# FrontPanel.net
KiCad netlist of a schematic drawn in Altium Designer
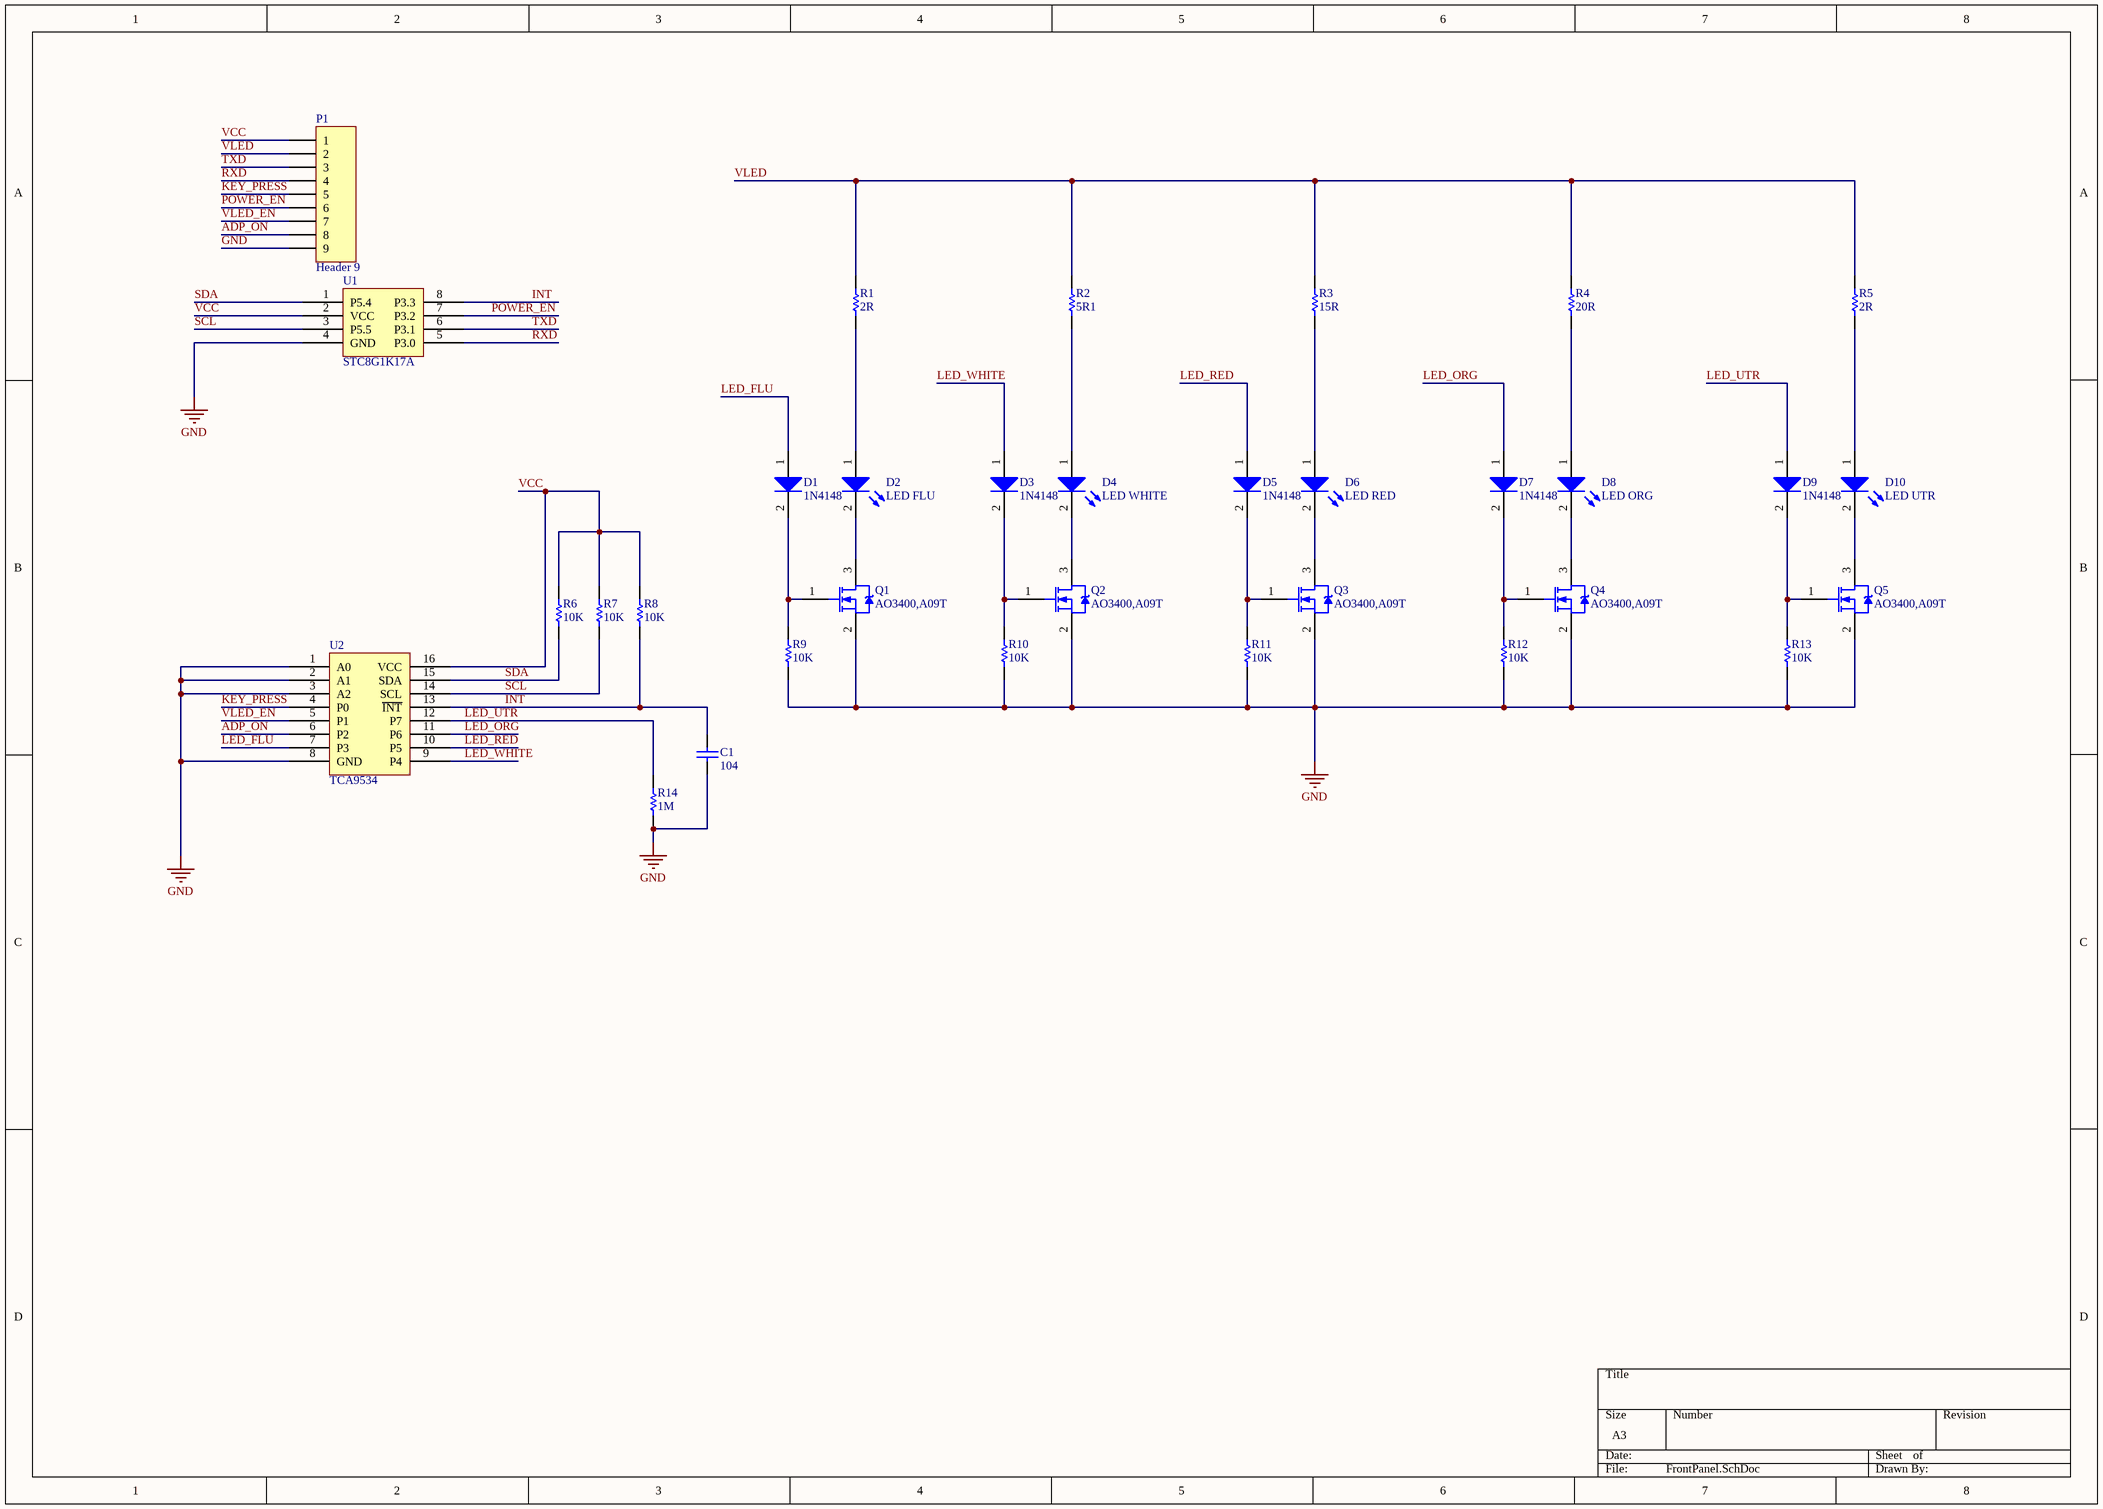
[diagram p0: FrontPanel.SchDoc]

(export (version "E")
  (design (tool "Eeschema 10.0.6"))
  (components
    (comp (ref "C1")
      (value "104")
      (footprint "FireFly:CAPC1608L")
      (description "Capacitor")
      (fields (field (name "PUBLISHER") "Altium Limited"))
      (libsource (lib "Miscellaneous Devices") (part "Cap"))
    )
    (comp (ref "D1")
      (value "1N4148")
      (footprint "FireFly:CD3216-1206")
      (description "Default Diode")
      (fields (field (name "PUBLISHER") "Altium Limited"))
      (libsource (lib "Miscellaneous Devices") (part "Diode"))
    )
    (comp (ref "D2")
      (value "LED FLU")
      (footprint "FireFly:LEDCHIP2835")
      (description "Typical INFRARED GaAs LED")
      (fields (field (name "PUBLISHER") "Altium Limited"))
      (libsource (lib "Miscellaneous Devices") (part "LED0"))
    )
    (comp (ref "D3")
      (value "1N4148")
      (footprint "FireFly:CD3216-1206")
      (description "Default Diode")
      (fields (field (name "PUBLISHER") "Altium Limited"))
      (libsource (lib "Miscellaneous Devices") (part "Diode"))
    )
    (comp (ref "D4")
      (value "LED WHITE")
      (footprint "FireFly:LEDCHIP2835")
      (description "Typical INFRARED GaAs LED")
      (fields (field (name "PUBLISHER") "Altium Limited"))
      (libsource (lib "Miscellaneous Devices") (part "LED0"))
    )
    (comp (ref "D5")
      (value "1N4148")
      (footprint "FireFly:CD3216-1206")
      (description "Default Diode")
      (fields (field (name "PUBLISHER") "Altium Limited"))
      (libsource (lib "Miscellaneous Devices") (part "Diode"))
    )
    (comp (ref "D6")
      (value "LED RED")
      (footprint "FireFly:LEDCHIP2835")
      (description "Typical INFRARED GaAs LED")
      (fields (field (name "PUBLISHER") "Altium Limited"))
      (libsource (lib "Miscellaneous Devices") (part "LED0"))
    )
    (comp (ref "D7")
      (value "1N4148")
      (footprint "FireFly:CD3216-1206")
      (description "Default Diode")
      (fields (field (name "PUBLISHER") "Altium Limited"))
      (libsource (lib "Miscellaneous Devices") (part "Diode"))
    )
    (comp (ref "D8")
      (value "LED ORG")
      (footprint "FireFly:LEDCHIP2835")
      (description "Typical INFRARED GaAs LED")
      (fields (field (name "PUBLISHER") "Altium Limited"))
      (libsource (lib "Miscellaneous Devices") (part "LED0"))
    )
    (comp (ref "D9")
      (value "1N4148")
      (footprint "FireFly:CD3216-1206")
      (description "Default Diode")
      (fields (field (name "PUBLISHER") "Altium Limited"))
      (libsource (lib "Miscellaneous Devices") (part "Diode"))
    )
    (comp (ref "D10")
      (value "LED UTR")
      (footprint "FireFly:LEDCHIP2835")
      (description "Typical INFRARED GaAs LED")
      (fields (field (name "PUBLISHER") "Altium Limited"))
      (libsource (lib "Miscellaneous Devices") (part "LED0"))
    )
    (comp (ref "P1")
      (value "Header 9")
      (footprint "HDR1X9")
      (description "Header, 9-Pin")
      (fields (field (name "PUBLISHER") "Altium Limited"))
      (libsource (lib "Miscellaneous Connectors") (part "Header 9"))
    )
    (comp (ref "Q1")
      (value "AO3400,A09T")
      (footprint "FireFly:SOT-23B_L")
      (description "N-Channel Power MOSFET")
      (fields (field (name "PUBLISHER") "Altium Limited"))
      (libsource (lib "Miscellaneous Devices") (part "NMOS-2"))
    )
    (comp (ref "Q2")
      (value "AO3400,A09T")
      (footprint "FireFly:SOT-23B_L")
      (description "N-Channel Power MOSFET")
      (fields (field (name "PUBLISHER") "Altium Limited"))
      (libsource (lib "Miscellaneous Devices") (part "NMOS-2"))
    )
    (comp (ref "Q3")
      (value "AO3400,A09T")
      (footprint "FireFly:SOT-23B_L")
      (description "N-Channel Power MOSFET")
      (fields (field (name "PUBLISHER") "Altium Limited"))
      (libsource (lib "Miscellaneous Devices") (part "NMOS-2"))
    )
    (comp (ref "Q4")
      (value "AO3400,A09T")
      (footprint "FireFly:SOT-23B_L")
      (description "N-Channel Power MOSFET")
      (fields (field (name "PUBLISHER") "Altium Limited"))
      (libsource (lib "Miscellaneous Devices") (part "NMOS-2"))
    )
    (comp (ref "Q5")
      (value "AO3400,A09T")
      (footprint "FireFly:SOT-23B_L")
      (description "N-Channel Power MOSFET")
      (fields (field (name "PUBLISHER") "Altium Limited"))
      (libsource (lib "Miscellaneous Devices") (part "NMOS-2"))
    )
    (comp (ref "R1")
      (value "2R")
      (footprint "FireFly:RESC1608L")
      (description "Resistor")
      (fields (field (name "PUBLISHER") "Altium Limited"))
      (libsource (lib "Miscellaneous Devices") (part "Res1"))
    )
    (comp (ref "R2")
      (value "5R1")
      (footprint "FireFly:RESC1608L")
      (description "Resistor")
      (fields (field (name "PUBLISHER") "Altium Limited"))
      (libsource (lib "Miscellaneous Devices") (part "Res1"))
    )
    (comp (ref "R3")
      (value "15R")
      (footprint "FireFly:RESC1608L")
      (description "Resistor")
      (fields (field (name "PUBLISHER") "Altium Limited"))
      (libsource (lib "Miscellaneous Devices") (part "Res1"))
    )
    (comp (ref "R4")
      (value "20R")
      (footprint "FireFly:RESC1608L")
      (description "Resistor")
      (fields (field (name "PUBLISHER") "Altium Limited"))
      (libsource (lib "Miscellaneous Devices") (part "Res1"))
    )
    (comp (ref "R5")
      (value "2R")
      (footprint "FireFly:RESC1608L")
      (description "Resistor")
      (fields (field (name "PUBLISHER") "Altium Limited"))
      (libsource (lib "Miscellaneous Devices") (part "Res1"))
    )
    (comp (ref "R6")
      (value "10K")
      (footprint "FireFly:RESC1608L")
      (description "Resistor")
      (fields (field (name "PUBLISHER") "Altium Limited"))
      (libsource (lib "Miscellaneous Devices") (part "Res1"))
    )
    (comp (ref "R7")
      (value "10K")
      (footprint "FireFly:RESC1608L")
      (description "Resistor")
      (fields (field (name "PUBLISHER") "Altium Limited"))
      (libsource (lib "Miscellaneous Devices") (part "Res1"))
    )
    (comp (ref "R8")
      (value "10K")
      (footprint "FireFly:RESC1608L")
      (description "Resistor")
      (fields (field (name "PUBLISHER") "Altium Limited"))
      (libsource (lib "Miscellaneous Devices") (part "Res1"))
    )
    (comp (ref "R9")
      (value "10K")
      (footprint "FireFly:RESC1608L")
      (description "Resistor")
      (fields (field (name "PUBLISHER") "Altium Limited"))
      (libsource (lib "Miscellaneous Devices") (part "Res1"))
    )
    (comp (ref "R10")
      (value "10K")
      (footprint "FireFly:RESC1608L")
      (description "Resistor")
      (fields (field (name "PUBLISHER") "Altium Limited"))
      (libsource (lib "Miscellaneous Devices") (part "Res1"))
    )
    (comp (ref "R11")
      (value "10K")
      (footprint "FireFly:RESC1608L")
      (description "Resistor")
      (fields (field (name "PUBLISHER") "Altium Limited"))
      (libsource (lib "Miscellaneous Devices") (part "Res1"))
    )
    (comp (ref "R12")
      (value "10K")
      (footprint "FireFly:RESC1608L")
      (description "Resistor")
      (fields (field (name "PUBLISHER") "Altium Limited"))
      (libsource (lib "Miscellaneous Devices") (part "Res1"))
    )
    (comp (ref "R13")
      (value "10K")
      (footprint "FireFly:RESC1608L")
      (description "Resistor")
      (fields (field (name "PUBLISHER") "Altium Limited"))
      (libsource (lib "Miscellaneous Devices") (part "Res1"))
    )
    (comp (ref "R14")
      (value "1M")
      (footprint "FireFly:RESC1608L")
      (description "Resistor")
      (fields (field (name "PUBLISHER") "Altium Limited"))
      (libsource (lib "Miscellaneous Devices") (part "Res1"))
    )
    (comp (ref "U1")
      (value "STC8G1K17A")
      (footprint "FireFly:SOP127P780-8M")
      (libsource (lib "FireFly") (part "STC8G1K17A"))
    )
    (comp (ref "U2")
      (value "TCA9534")
      (footprint "FireFly:TSOP65P640-16AM")
      (libsource (lib "FireFly") (part "TCA9534"))
    )
  )
  (nets
    (net (code "1") (name "/ADP_ON") (class "Default")
      (node (ref "P1") (pin "8") (pinfunction "8_8") (pintype "passive"))
      (node (ref "U2") (pin "6") (pinfunction "P2_6") (pintype "passive"))
    )
    (net (code "2") (name "/INT") (class "Default")
      (node (ref "C1") (pin "1") (pinfunction "1_1") (pintype "passive"))
      (node (ref "R8") (pin "2") (pinfunction "2_2") (pintype "passive"))
      (node (ref "U1") (pin "8") (pinfunction "P3.3_8") (pintype "passive"))
      (node (ref "U2") (pin "13") (pinfunction "~{INT}_13") (pintype "passive"))
    )
    (net (code "3") (name "/KEY_PRESS") (class "Default")
      (node (ref "P1") (pin "5") (pinfunction "5_5") (pintype "passive"))
      (node (ref "U2") (pin "4") (pinfunction "P0_4") (pintype "passive"))
    )
    (net (code "4") (name "/LED_FLU") (class "Default")
      (node (ref "D1") (pin "1") (pinfunction "A_1") (pintype "passive"))
      (node (ref "U2") (pin "7") (pinfunction "P3_7") (pintype "passive"))
    )
    (net (code "5") (name "/LED_ORG") (class "Default")
      (node (ref "D7") (pin "1") (pinfunction "A_1") (pintype "passive"))
      (node (ref "U2") (pin "11") (pinfunction "P6_11") (pintype "passive"))
    )
    (net (code "6") (name "/LED_RED") (class "Default")
      (node (ref "D5") (pin "1") (pinfunction "A_1") (pintype "passive"))
      (node (ref "U2") (pin "10") (pinfunction "P5_10") (pintype "passive"))
    )
    (net (code "7") (name "/LED_UTR") (class "Default")
      (node (ref "D9") (pin "1") (pinfunction "A_1") (pintype "passive"))
      (node (ref "R14") (pin "1") (pinfunction "1_1") (pintype "passive"))
      (node (ref "U2") (pin "12") (pinfunction "P7_12") (pintype "passive"))
    )
    (net (code "8") (name "/LED_WHITE") (class "Default")
      (node (ref "D3") (pin "1") (pinfunction "A_1") (pintype "passive"))
      (node (ref "U2") (pin "9") (pinfunction "P4_9") (pintype "passive"))
    )
    (net (code "9") (name "/POWER_EN") (class "Default")
      (node (ref "P1") (pin "6") (pinfunction "6_6") (pintype "passive"))
      (node (ref "U1") (pin "7") (pinfunction "P3.2_7") (pintype "passive"))
    )
    (net (code "10") (name "/RXD") (class "Default")
      (node (ref "P1") (pin "4") (pinfunction "4_4") (pintype "passive"))
      (node (ref "U1") (pin "5") (pinfunction "P3.0_5") (pintype "passive"))
    )
    (net (code "11") (name "/SCL") (class "Default")
      (node (ref "R7") (pin "2") (pinfunction "2_2") (pintype "passive"))
      (node (ref "U1") (pin "3") (pinfunction "P5.5_3") (pintype "passive"))
      (node (ref "U2") (pin "14") (pinfunction "SCL_14") (pintype "passive"))
    )
    (net (code "12") (name "/SDA") (class "Default")
      (node (ref "R6") (pin "2") (pinfunction "2_2") (pintype "passive"))
      (node (ref "U1") (pin "1") (pinfunction "P5.4_1") (pintype "passive"))
      (node (ref "U2") (pin "15") (pinfunction "SDA_15") (pintype "passive"))
    )
    (net (code "13") (name "/TXD") (class "Default")
      (node (ref "P1") (pin "3") (pinfunction "3_3") (pintype "passive"))
      (node (ref "U1") (pin "6") (pinfunction "P3.1_6") (pintype "passive"))
    )
    (net (code "14") (name "/VCC") (class "Default")
      (node (ref "P1") (pin "1") (pinfunction "1_1") (pintype "passive"))
      (node (ref "R6") (pin "1") (pinfunction "1_1") (pintype "passive"))
      (node (ref "R7") (pin "1") (pinfunction "1_1") (pintype "passive"))
      (node (ref "R8") (pin "1") (pinfunction "1_1") (pintype "passive"))
      (node (ref "U1") (pin "2") (pinfunction "VCC_2") (pintype "passive"))
      (node (ref "U2") (pin "16") (pinfunction "VCC_16") (pintype "passive"))
    )
    (net (code "15") (name "/VLED") (class "Default")
      (node (ref "P1") (pin "2") (pinfunction "2_2") (pintype "passive"))
      (node (ref "R1") (pin "1") (pinfunction "1_1") (pintype "passive"))
      (node (ref "R2") (pin "1") (pinfunction "1_1") (pintype "passive"))
      (node (ref "R3") (pin "1") (pinfunction "1_1") (pintype "passive"))
      (node (ref "R4") (pin "1") (pinfunction "1_1") (pintype "passive"))
      (node (ref "R5") (pin "1") (pinfunction "1_1") (pintype "passive"))
    )
    (net (code "16") (name "/VLED_EN") (class "Default")
      (node (ref "P1") (pin "7") (pinfunction "7_7") (pintype "passive"))
      (node (ref "U2") (pin "5") (pinfunction "P1_5") (pintype "passive"))
    )
    (net (code "17") (name "GND") (class "Default")
      (node (ref "C1") (pin "2") (pinfunction "2_2") (pintype "passive"))
      (node (ref "P1") (pin "9") (pinfunction "9_9") (pintype "passive"))
      (node (ref "Q1") (pin "2") (pinfunction "S_2") (pintype "passive"))
      (node (ref "Q2") (pin "2") (pinfunction "S_2") (pintype "passive"))
      (node (ref "Q3") (pin "2") (pinfunction "S_2") (pintype "passive"))
      (node (ref "Q4") (pin "2") (pinfunction "S_2") (pintype "passive"))
      (node (ref "Q5") (pin "2") (pinfunction "S_2") (pintype "passive"))
      (node (ref "R10") (pin "2") (pinfunction "2_2") (pintype "passive"))
      (node (ref "R11") (pin "2") (pinfunction "2_2") (pintype "passive"))
      (node (ref "R12") (pin "2") (pinfunction "2_2") (pintype "passive"))
      (node (ref "R13") (pin "2") (pinfunction "2_2") (pintype "passive"))
      (node (ref "R14") (pin "2") (pinfunction "2_2") (pintype "passive"))
      (node (ref "R9") (pin "2") (pinfunction "2_2") (pintype "passive"))
      (node (ref "U1") (pin "4") (pinfunction "GND_4") (pintype "passive"))
      (node (ref "U2") (pin "1") (pinfunction "A0_1") (pintype "passive"))
      (node (ref "U2") (pin "2") (pinfunction "A1_2") (pintype "passive"))
      (node (ref "U2") (pin "3") (pinfunction "A2_3") (pintype "passive"))
      (node (ref "U2") (pin "8") (pinfunction "GND_8") (pintype "passive"))
    )
    (net (code "18") (name "Net-(D1-K)") (class "Default")
      (node (ref "D1") (pin "2") (pinfunction "K_2") (pintype "passive"))
      (node (ref "Q1") (pin "1") (pinfunction "G_1") (pintype "passive"))
      (node (ref "R9") (pin "1") (pinfunction "1_1") (pintype "passive"))
    )
    (net (code "19") (name "Net-(D2-A)") (class "Default")
      (node (ref "D2") (pin "1") (pinfunction "A_1") (pintype "passive"))
      (node (ref "R1") (pin "2") (pinfunction "2_2") (pintype "passive"))
    )
    (net (code "20") (name "Net-(D2-K)") (class "Default")
      (node (ref "D2") (pin "2") (pinfunction "K_2") (pintype "passive"))
      (node (ref "Q1") (pin "3") (pinfunction "D_3") (pintype "passive"))
    )
    (net (code "21") (name "Net-(D3-K)") (class "Default")
      (node (ref "D3") (pin "2") (pinfunction "K_2") (pintype "passive"))
      (node (ref "Q2") (pin "1") (pinfunction "G_1") (pintype "passive"))
      (node (ref "R10") (pin "1") (pinfunction "1_1") (pintype "passive"))
    )
    (net (code "22") (name "Net-(D4-A)") (class "Default")
      (node (ref "D4") (pin "1") (pinfunction "A_1") (pintype "passive"))
      (node (ref "R2") (pin "2") (pinfunction "2_2") (pintype "passive"))
    )
    (net (code "23") (name "Net-(D4-K)") (class "Default")
      (node (ref "D4") (pin "2") (pinfunction "K_2") (pintype "passive"))
      (node (ref "Q2") (pin "3") (pinfunction "D_3") (pintype "passive"))
    )
    (net (code "24") (name "Net-(D5-K)") (class "Default")
      (node (ref "D5") (pin "2") (pinfunction "K_2") (pintype "passive"))
      (node (ref "Q3") (pin "1") (pinfunction "G_1") (pintype "passive"))
      (node (ref "R11") (pin "1") (pinfunction "1_1") (pintype "passive"))
    )
    (net (code "25") (name "Net-(D6-A)") (class "Default")
      (node (ref "D6") (pin "1") (pinfunction "A_1") (pintype "passive"))
      (node (ref "R3") (pin "2") (pinfunction "2_2") (pintype "passive"))
    )
    (net (code "26") (name "Net-(D6-K)") (class "Default")
      (node (ref "D6") (pin "2") (pinfunction "K_2") (pintype "passive"))
      (node (ref "Q3") (pin "3") (pinfunction "D_3") (pintype "passive"))
    )
    (net (code "27") (name "Net-(D7-K)") (class "Default")
      (node (ref "D7") (pin "2") (pinfunction "K_2") (pintype "passive"))
      (node (ref "Q4") (pin "1") (pinfunction "G_1") (pintype "passive"))
      (node (ref "R12") (pin "1") (pinfunction "1_1") (pintype "passive"))
    )
    (net (code "28") (name "Net-(D8-A)") (class "Default")
      (node (ref "D8") (pin "1") (pinfunction "A_1") (pintype "passive"))
      (node (ref "R4") (pin "2") (pinfunction "2_2") (pintype "passive"))
    )
    (net (code "29") (name "Net-(D8-K)") (class "Default")
      (node (ref "D8") (pin "2") (pinfunction "K_2") (pintype "passive"))
      (node (ref "Q4") (pin "3") (pinfunction "D_3") (pintype "passive"))
    )
    (net (code "30") (name "Net-(D9-K)") (class "Default")
      (node (ref "D9") (pin "2") (pinfunction "K_2") (pintype "passive"))
      (node (ref "Q5") (pin "1") (pinfunction "G_1") (pintype "passive"))
      (node (ref "R13") (pin "1") (pinfunction "1_1") (pintype "passive"))
    )
    (net (code "31") (name "Net-(D10-A)") (class "Default")
      (node (ref "D10") (pin "1") (pinfunction "A_1") (pintype "passive"))
      (node (ref "R5") (pin "2") (pinfunction "2_2") (pintype "passive"))
    )
    (net (code "32") (name "Net-(D10-K)") (class "Default")
      (node (ref "D10") (pin "2") (pinfunction "K_2") (pintype "passive"))
      (node (ref "Q5") (pin "3") (pinfunction "D_3") (pintype "passive"))
    )
  )
)
